# 5_Sensors.net
KiCad netlist of a schematic drawn in Altium Designer
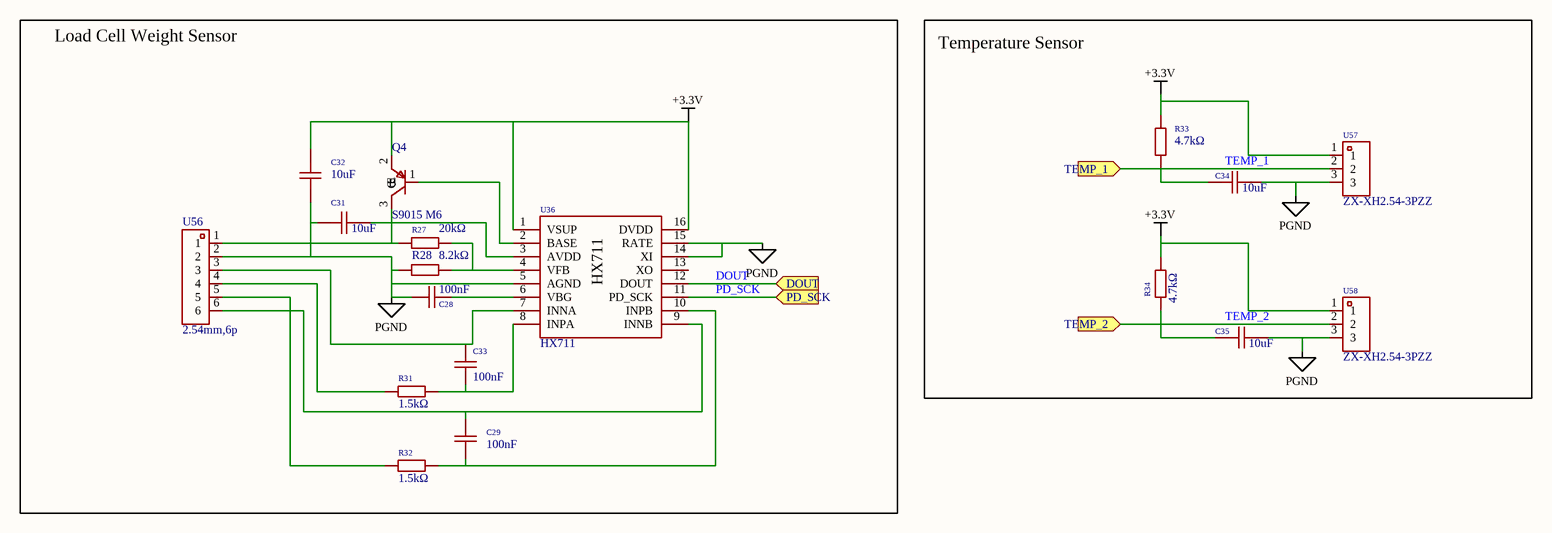
[diagram p0: 5_Sensors.schdoc]

(export (version "E")
  (design (tool "Eeschema 10.0.6"))
  (components
    (comp (ref "C28")
      (value "100nF")
      (footprint "C0603")
      (fields
        (field (name "MANUFACTURER") "FH(风华)")
        (field (name "MANUFACTURER PART") "0603B104K500NT")
        (field (name "TOLERANCE") "±10%")
      )
      (libsource (lib "altium-import") (part "root_0_0603B104K500NT_C30926_"))
    )
    (comp (ref "C29")
      (value "100nF")
      (footprint "C0603")
      (fields
        (field (name "MANUFACTURER") "FH(风华)")
        (field (name "MANUFACTURER PART") "0603B104K500NT")
        (field (name "TOLERANCE") "±10%")
      )
      (libsource (lib "altium-import") (part "root_1_0603B104K500NT_C30926_"))
    )
    (comp (ref "C31")
      (value "10uF")
      (footprint "C0603")
      (fields
        (field (name "MANUFACTURER") "SAMSUNG(三星)")
        (field (name "MANUFACTURER PART") "CL10A106KP8NNNC")
        (field (name "TOLERANCE") "±10%")
      )
      (libsource (lib "altium-import") (part "root_0_CL10A106KP8NNNC_"))
    )
    (comp (ref "C32")
      (value "10uF")
      (footprint "C0603")
      (fields
        (field (name "MANUFACTURER") "SAMSUNG(三星)")
        (field (name "MANUFACTURER PART") "CL10A106KP8NNNC")
        (field (name "TOLERANCE") "±10%")
      )
      (libsource (lib "altium-import") (part "root_1_CL10A106KP8NNNC_"))
    )
    (comp (ref "C33")
      (value "100nF")
      (footprint "C0603")
      (fields
        (field (name "MANUFACTURER") "FH(风华)")
        (field (name "MANUFACTURER PART") "0603B104K500NT")
        (field (name "TOLERANCE") "±10%")
      )
      (libsource (lib "altium-import") (part "root_1_0603B104K500NT_C30926_"))
    )
    (comp (ref "C34")
      (value "10uF")
      (footprint "C0603")
      (fields
        (field (name "MANUFACTURER") "SAMSUNG(三星)")
        (field (name "MANUFACTURER PART") "CL10A106KP8NNNC")
        (field (name "TOLERANCE") "±10%")
      )
      (libsource (lib "altium-import") (part "root_0_CL10A106KP8NNNC_"))
    )
    (comp (ref "C35")
      (value "10uF")
      (footprint "C0603")
      (fields
        (field (name "MANUFACTURER") "SAMSUNG(三星)")
        (field (name "MANUFACTURER PART") "CL10A106KP8NNNC")
        (field (name "TOLERANCE") "±10%")
      )
      (libsource (lib "altium-import") (part "root_0_CL10A106KP8NNNC_"))
    )
    (comp (ref "Q4")
      (value "S9015 M6")
      (footprint "SOT-23-3_L2.9-W1.3-P1.90-LS2.4-BR")
      (fields (field (name "MANUFACTURER") "FOSAN(富信)"))
      (libsource (lib "altium-import") (part "root_2_S9015 M6_"))
    )
    (comp (ref "R27")
      (value "20kΩ")
      (footprint "R0603")
      (fields
        (field (name "MANUFACTURER") "UNI-ROYAL(厚声)")
        (field (name "MANUFACTURER PART") "0603WAF2002T5E")
        (field (name "TOLERANCE") "±1%")
      )
      (libsource (lib "altium-import") (part "root_0_0603WAF2002T5E_"))
    )
    (comp (ref "R28")
      (value "8.2kΩ")
      (footprint "R0603")
      (fields
        (field (name "MANUFACTURER") "YAGEO(国巨)")
        (field (name "MANUFACTURER PART") "RC0603FR-078K2L")
        (field (name "TOLERANCE") "±1%")
      )
      (libsource (lib "altium-import") (part "root_0_RC0603FR-078K2L_"))
    )
    (comp (ref "R31")
      (value "1.5kΩ")
      (footprint "R0402")
      (fields
        (field (name "MANUFACTURER") "UNI-ROYAL(厚声)")
        (field (name "MANUFACTURER PART") "0402WGJ0152TCE")
        (field (name "TOLERANCE") "±5%")
      )
      (libsource (lib "altium-import") (part "root_0_0402WGJ0152TCE_"))
    )
    (comp (ref "R32")
      (value "1.5kΩ")
      (footprint "R0402")
      (fields
        (field (name "MANUFACTURER") "UNI-ROYAL(厚声)")
        (field (name "MANUFACTURER PART") "0402WGJ0152TCE")
        (field (name "TOLERANCE") "±5%")
      )
      (libsource (lib "altium-import") (part "root_0_0402WGJ0152TCE_"))
    )
    (comp (ref "R33")
      (value "4.7kΩ")
      (footprint "R0402")
      (fields
        (field (name "MANUFACTURER") "UNI-ROYAL(厚声)")
        (field (name "MANUFACTURER PART") "0402WGF4701TCE")
        (field (name "TOLERANCE") "±1%")
      )
      (libsource (lib "altium-import") (part "root_3_0402WGF4701TCE_"))
    )
    (comp (ref "R34")
      (value "4.7kΩ")
      (footprint "R0402")
      (fields
        (field (name "MANUFACTURER") "UNI-ROYAL(厚声)")
        (field (name "MANUFACTURER PART") "0402WGF4701TCE")
        (field (name "TOLERANCE") "±1%")
      )
      (libsource (lib "altium-import") (part "root_1_0402WGF4701TCE_"))
    )
    (comp (ref "U36")
      (value "HX711")
      (footprint "SOP-16_L10.0-W3.9-P1.27-LS6.0-BL")
      (fields (field (name "MANUFACTURER") "AVIA(海芯科技)"))
      (libsource (lib "altium-import") (part "root_0_HX711_"))
    )
    (comp (ref "U56")
      (value "2.54mm,6p")
      (footprint "HDR-TH_6P-P2.54-V-M-A")
      (libsource (lib "altium-import") (part "root_0_mirrored_长排针,2.54mm,6p_"))
    )
    (comp (ref "U57")
      (value "ZX-XH2.54-3PZZ")
      (footprint "CONN-TH_3P-P2.54_2501S-3P")
      (fields (field (name "MANUFACTURER") "Megastar(兆星)"))
      (libsource (lib "altium-import") (part "root_0_ZX-XH2.54-3PZZ_"))
    )
    (comp (ref "U58")
      (value "ZX-XH2.54-3PZZ")
      (footprint "CONN-TH_3P-P2.54_2501S-3P")
      (fields (field (name "MANUFACTURER") "Megastar(兆星)"))
      (libsource (lib "altium-import") (part "root_0_ZX-XH2.54-3PZZ_"))
    )
  )
  (nets
    (net (code "1") (name "+3.3V") (class "Default")
      (node (ref "C32") (pin "2") (pinfunction "2_2") (pintype "passive"))
      (node (ref "Q4") (pin "2") (pinfunction "E_2") (pintype "passive"))
      (node (ref "R33") (pin "1") (pinfunction "1_1") (pintype "passive"))
      (node (ref "R34") (pin "2") (pinfunction "2_2") (pintype "passive"))
      (node (ref "U36") (pin "1") (pinfunction "VSUP_1") (pintype "passive"))
      (node (ref "U36") (pin "16") (pinfunction "DVDD_16") (pintype "passive"))
      (node (ref "U57") (pin "1") (pinfunction "1_1") (pintype "passive"))
      (node (ref "U58") (pin "1") (pinfunction "1_1") (pintype "passive"))
    )
    (net (code "2") (name "/DOUT") (class "Default")
      (node (ref "U36") (pin "12") (pinfunction "DOUT_12") (pintype "passive"))
    )
    (net (code "3") (name "/PD_SCK") (class "Default")
      (node (ref "U36") (pin "11") (pinfunction "PD_SCK_11") (pintype "passive"))
    )
    (net (code "4") (name "/TEMP_1") (class "Default")
      (node (ref "C34") (pin "1") (pinfunction "1_1") (pintype "passive"))
      (node (ref "R33") (pin "2") (pinfunction "2_2") (pintype "passive"))
      (node (ref "U57") (pin "2") (pinfunction "2_2") (pintype "passive"))
    )
    (net (code "5") (name "/TEMP_2") (class "Default")
      (node (ref "C35") (pin "1") (pinfunction "1_1") (pintype "passive"))
      (node (ref "R34") (pin "1") (pinfunction "1_1") (pintype "passive"))
      (node (ref "U58") (pin "2") (pinfunction "2_2") (pintype "passive"))
    )
    (net (code "6") (name "Net-(Q4-B)") (class "Default")
      (node (ref "Q4") (pin "1") (pinfunction "B_1") (pintype "passive"))
      (node (ref "U36") (pin "2") (pinfunction "BASE_2") (pintype "passive"))
    )
    (net (code "7") (name "Net-(Q4-C)") (class "Default")
      (node (ref "C31") (pin "2") (pinfunction "2_2") (pintype "passive"))
      (node (ref "Q4") (pin "3") (pinfunction "C_3") (pintype "passive"))
      (node (ref "R27") (pin "1") (pinfunction "1_1") (pintype "passive"))
      (node (ref "U36") (pin "3") (pinfunction "AVDD_3") (pintype "passive"))
      (node (ref "U56") (pin "1") (pinfunction "1_1") (pintype "passive"))
    )
    (net (code "8") (name "Net-(R31-Pad1)") (class "Default")
      (node (ref "R31") (pin "1") (pinfunction "1_1") (pintype "passive"))
      (node (ref "U56") (pin "4") (pinfunction "4_4") (pintype "passive"))
    )
    (net (code "9") (name "Net-(R32-Pad1)") (class "Default")
      (node (ref "R32") (pin "1") (pinfunction "1_1") (pintype "passive"))
      (node (ref "U56") (pin "5") (pinfunction "5_5") (pintype "passive"))
    )
    (net (code "10") (name "Net-(U36-INNA)") (class "Default")
      (node (ref "C33") (pin "2") (pinfunction "2_2") (pintype "passive"))
      (node (ref "U36") (pin "7") (pinfunction "INNA_7") (pintype "passive"))
      (node (ref "U56") (pin "3") (pinfunction "3_3") (pintype "passive"))
    )
    (net (code "11") (name "Net-(U36-INNB)") (class "Default")
      (node (ref "C29") (pin "2") (pinfunction "2_2") (pintype "passive"))
      (node (ref "U36") (pin "9") (pinfunction "INNB_9") (pintype "passive"))
      (node (ref "U56") (pin "6") (pinfunction "6_6") (pintype "passive"))
    )
    (net (code "12") (name "Net-(U36-INPA)") (class "Default")
      (node (ref "C33") (pin "1") (pinfunction "1_1") (pintype "passive"))
      (node (ref "R31") (pin "2") (pinfunction "2_2") (pintype "passive"))
      (node (ref "U36") (pin "8") (pinfunction "INPA_8") (pintype "passive"))
    )
    (net (code "13") (name "Net-(U36-INPB)") (class "Default")
      (node (ref "C29") (pin "1") (pinfunction "1_1") (pintype "passive"))
      (node (ref "R32") (pin "2") (pinfunction "2_2") (pintype "passive"))
      (node (ref "U36") (pin "10") (pinfunction "INPB_10") (pintype "passive"))
    )
    (net (code "14") (name "Net-(U36-VBG)") (class "Default")
      (node (ref "C28") (pin "2") (pinfunction "2_2") (pintype "passive"))
      (node (ref "U36") (pin "6") (pinfunction "VBG_6") (pintype "passive"))
    )
    (net (code "15") (name "Net-(U36-VFB)") (class "Default")
      (node (ref "R27") (pin "2") (pinfunction "2_2") (pintype "passive"))
      (node (ref "R28") (pin "2") (pinfunction "2_2") (pintype "passive"))
      (node (ref "U36") (pin "4") (pinfunction "VFB_4") (pintype "passive"))
    )
    (net (code "16") (name "PGND") (class "Default")
      (node (ref "C28") (pin "1") (pinfunction "1_1") (pintype "passive"))
      (node (ref "C31") (pin "1") (pinfunction "1_1") (pintype "passive"))
      (node (ref "C32") (pin "1") (pinfunction "1_1") (pintype "passive"))
      (node (ref "C34") (pin "2") (pinfunction "2_2") (pintype "passive"))
      (node (ref "C35") (pin "2") (pinfunction "2_2") (pintype "passive"))
      (node (ref "R28") (pin "1") (pinfunction "1_1") (pintype "passive"))
      (node (ref "U36") (pin "14") (pinfunction "XI_14") (pintype "passive"))
      (node (ref "U36") (pin "15") (pinfunction "RATE_15") (pintype "passive"))
      (node (ref "U36") (pin "5") (pinfunction "AGND_5") (pintype "passive"))
      (node (ref "U56") (pin "2") (pinfunction "2_2") (pintype "passive"))
      (node (ref "U57") (pin "3") (pinfunction "3_3") (pintype "passive"))
      (node (ref "U58") (pin "3") (pinfunction "3_3") (pintype "passive"))
    )
    (net (code "17") (name "unconnected-(U36-XO-Pad13)") (class "Default")
      (node (ref "U36") (pin "13") (pinfunction "XO_13") (pintype "passive"))
    )
  )
)
